# PLT-01-RevB.net
KiCad netlist of a schematic drawn in EAGLE
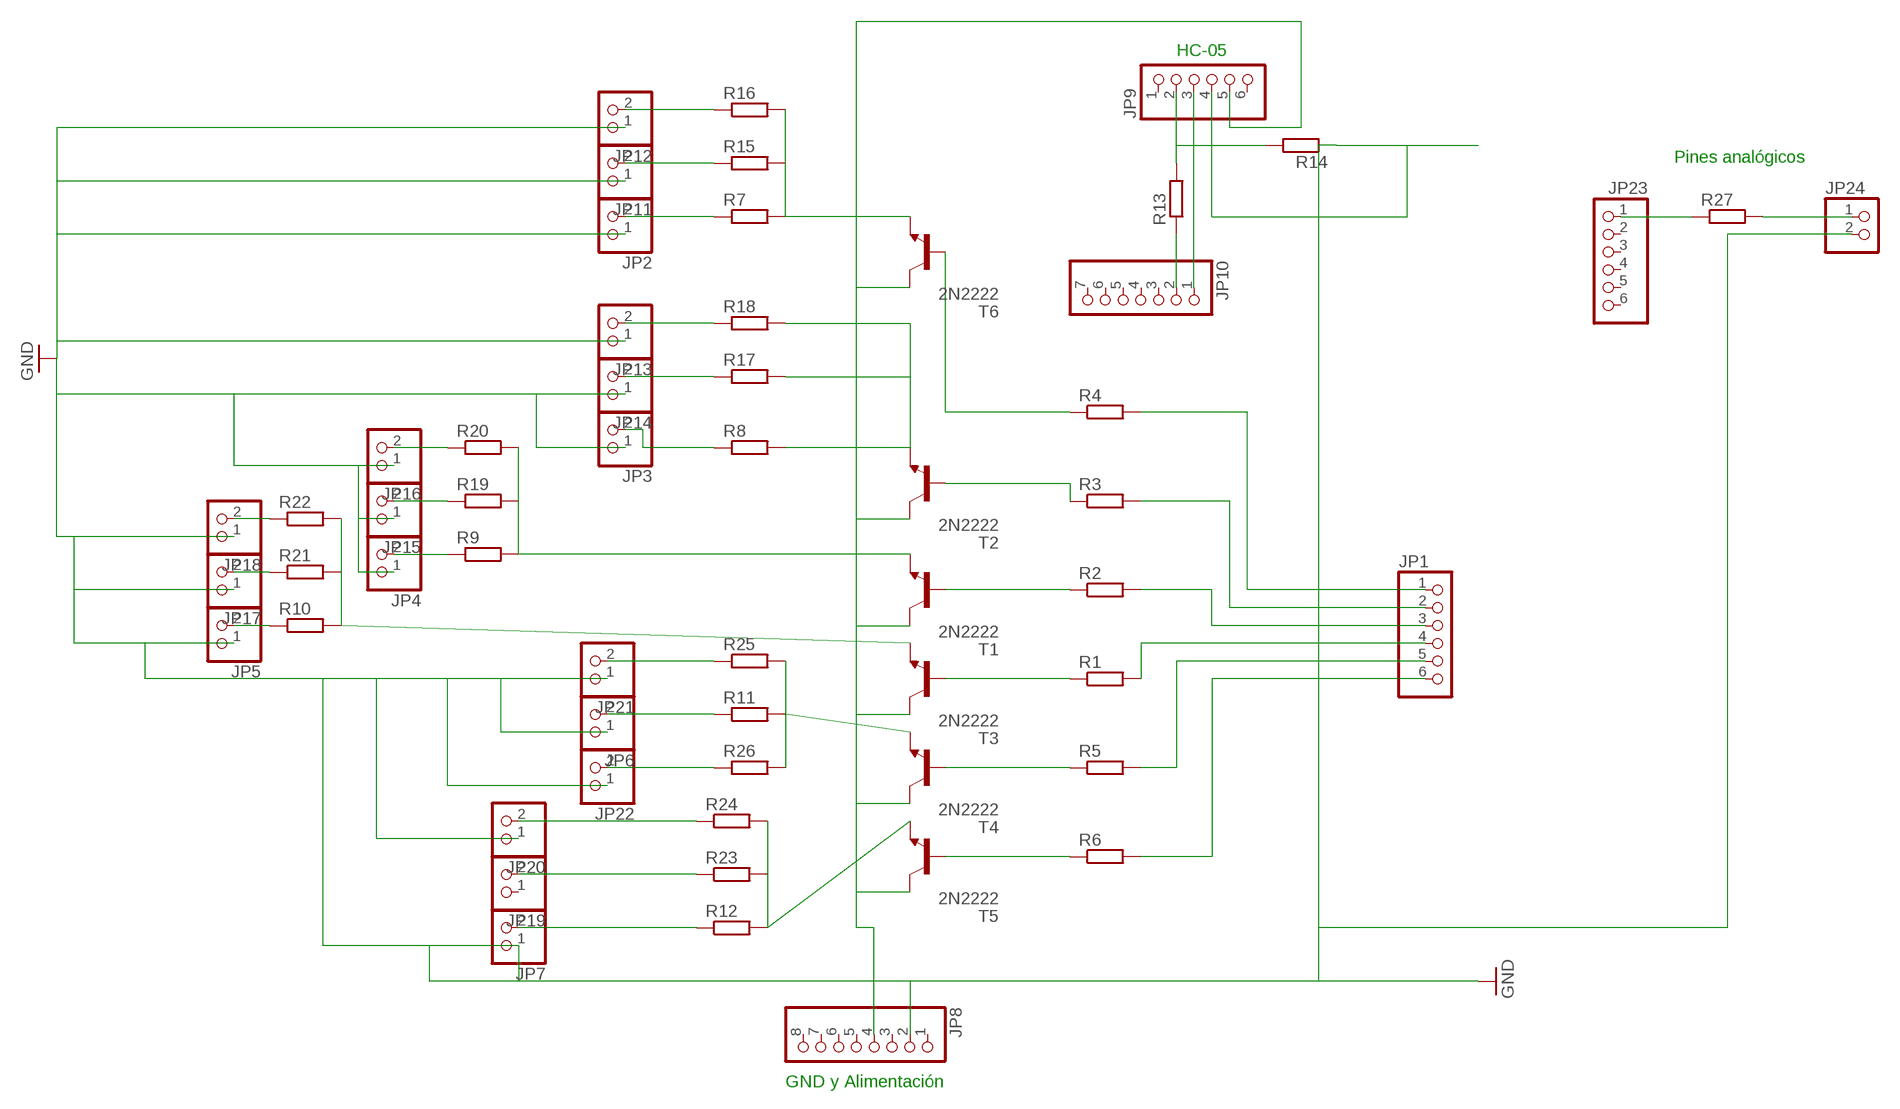
[diagram p0: schematic, sheet 1]

(export (version "E")
  (design (tool "Eeschema 10.0.6"))
  (components
    (comp (ref "JP1")
      (value "PINHD-1X6")
      (footprint "eagle-import:1X06")
      (libsource (lib "eagle-import") (part "PINHD-1X6"))
    )
    (comp (ref "JP2")
      (value "PINHD-1X2")
      (footprint "eagle-import:1X02")
      (libsource (lib "eagle-import") (part "PINHD-1X2"))
    )
    (comp (ref "JP3")
      (value "PINHD-1X2")
      (footprint "eagle-import:1X02")
      (libsource (lib "eagle-import") (part "PINHD-1X2"))
    )
    (comp (ref "JP4")
      (value "PINHD-1X2")
      (footprint "eagle-import:1X02")
      (libsource (lib "eagle-import") (part "PINHD-1X2"))
    )
    (comp (ref "JP5")
      (value "PINHD-1X2")
      (footprint "eagle-import:1X02")
      (libsource (lib "eagle-import") (part "PINHD-1X2"))
    )
    (comp (ref "JP6")
      (value "PINHD-1X2")
      (footprint "eagle-import:1X02")
      (libsource (lib "eagle-import") (part "PINHD-1X2"))
    )
    (comp (ref "JP7")
      (value "PINHD-1X2")
      (footprint "eagle-import:1X02")
      (libsource (lib "eagle-import") (part "PINHD-1X2"))
    )
    (comp (ref "JP8")
      (value "PINHD-1X8")
      (footprint "eagle-import:1X08")
      (libsource (lib "eagle-import") (part "PINHD-1X8"))
    )
    (comp (ref "JP9")
      (value "PINHD-1X6")
      (footprint "eagle-import:1X06")
      (libsource (lib "eagle-import") (part "PINHD-1X6"))
    )
    (comp (ref "JP10")
      (value "PINHD-1X7")
      (footprint "eagle-import:1X07")
      (libsource (lib "eagle-import") (part "PINHD-1X7"))
    )
    (comp (ref "JP11")
      (value "PINHD-1X2")
      (footprint "eagle-import:1X02")
      (libsource (lib "eagle-import") (part "PINHD-1X2"))
    )
    (comp (ref "JP12")
      (value "PINHD-1X2")
      (footprint "eagle-import:1X02")
      (libsource (lib "eagle-import") (part "PINHD-1X2"))
    )
    (comp (ref "JP13")
      (value "PINHD-1X2")
      (footprint "eagle-import:1X02")
      (libsource (lib "eagle-import") (part "PINHD-1X2"))
    )
    (comp (ref "JP14")
      (value "PINHD-1X2")
      (footprint "eagle-import:1X02")
      (libsource (lib "eagle-import") (part "PINHD-1X2"))
    )
    (comp (ref "JP15")
      (value "PINHD-1X2")
      (footprint "eagle-import:1X02")
      (libsource (lib "eagle-import") (part "PINHD-1X2"))
    )
    (comp (ref "JP16")
      (value "PINHD-1X2")
      (footprint "eagle-import:1X02")
      (libsource (lib "eagle-import") (part "PINHD-1X2"))
    )
    (comp (ref "JP17")
      (value "PINHD-1X2")
      (footprint "eagle-import:1X02")
      (libsource (lib "eagle-import") (part "PINHD-1X2"))
    )
    (comp (ref "JP18")
      (value "PINHD-1X2")
      (footprint "eagle-import:1X02")
      (libsource (lib "eagle-import") (part "PINHD-1X2"))
    )
    (comp (ref "JP19")
      (value "PINHD-1X2")
      (footprint "eagle-import:1X02")
      (libsource (lib "eagle-import") (part "PINHD-1X2"))
    )
    (comp (ref "JP20")
      (value "PINHD-1X2")
      (footprint "eagle-import:1X02")
      (libsource (lib "eagle-import") (part "PINHD-1X2"))
    )
    (comp (ref "JP21")
      (value "PINHD-1X2")
      (footprint "eagle-import:1X02")
      (libsource (lib "eagle-import") (part "PINHD-1X2"))
    )
    (comp (ref "JP22")
      (value "PINHD-1X2")
      (footprint "eagle-import:1X02")
      (libsource (lib "eagle-import") (part "PINHD-1X2"))
    )
    (comp (ref "JP23")
      (value "PINHD-1X6")
      (footprint "eagle-import:1X06")
      (libsource (lib "eagle-import") (part "PINHD-1X6"))
    )
    (comp (ref "JP24")
      (value "PINHD-1X2")
      (footprint "eagle-import:1X02")
      (libsource (lib "eagle-import") (part "PINHD-1X2"))
    )
    (comp (ref "R1")
      (value "R-EU_0207/10")
      (footprint "eagle-import:0207_10")
      (libsource (lib "eagle-import") (part "R-EU_0207/10"))
    )
    (comp (ref "R2")
      (value "R-EU_0207/10")
      (footprint "eagle-import:0207_10")
      (libsource (lib "eagle-import") (part "R-EU_0207/10"))
    )
    (comp (ref "R3")
      (value "R-EU_0207/10")
      (footprint "eagle-import:0207_10")
      (libsource (lib "eagle-import") (part "R-EU_0207/10"))
    )
    (comp (ref "R4")
      (value "R-EU_0207/10")
      (footprint "eagle-import:0207_10")
      (libsource (lib "eagle-import") (part "R-EU_0207/10"))
    )
    (comp (ref "R5")
      (value "R-EU_0207/10")
      (footprint "eagle-import:0207_10")
      (libsource (lib "eagle-import") (part "R-EU_0207/10"))
    )
    (comp (ref "R6")
      (value "R-EU_0207/10")
      (footprint "eagle-import:0207_10")
      (libsource (lib "eagle-import") (part "R-EU_0207/10"))
    )
    (comp (ref "R7")
      (value "R-EU_0207/10")
      (footprint "eagle-import:0207_10")
      (libsource (lib "eagle-import") (part "R-EU_0207/10"))
    )
    (comp (ref "R8")
      (value "R-EU_0207/10")
      (footprint "eagle-import:0207_10")
      (libsource (lib "eagle-import") (part "R-EU_0207/10"))
    )
    (comp (ref "R9")
      (value "R-EU_0207/10")
      (footprint "eagle-import:0207_10")
      (libsource (lib "eagle-import") (part "R-EU_0207/10"))
    )
    (comp (ref "R10")
      (value "R-EU_0207/10")
      (footprint "eagle-import:0207_10")
      (libsource (lib "eagle-import") (part "R-EU_0207/10"))
    )
    (comp (ref "R11")
      (value "R-EU_0207/10")
      (footprint "eagle-import:0207_10")
      (libsource (lib "eagle-import") (part "R-EU_0207/10"))
    )
    (comp (ref "R12")
      (value "R-EU_0207/10")
      (footprint "eagle-import:0207_10")
      (libsource (lib "eagle-import") (part "R-EU_0207/10"))
    )
    (comp (ref "R13")
      (value "R-EU_0207/10")
      (footprint "eagle-import:0207_10")
      (libsource (lib "eagle-import") (part "R-EU_0207/10"))
    )
    (comp (ref "R14")
      (value "R-EU_0207/10")
      (footprint "eagle-import:0207_10")
      (libsource (lib "eagle-import") (part "R-EU_0207/10"))
    )
    (comp (ref "R15")
      (value "R-EU_0207/10")
      (footprint "eagle-import:0207_10")
      (libsource (lib "eagle-import") (part "R-EU_0207/10"))
    )
    (comp (ref "R16")
      (value "R-EU_0207/10")
      (footprint "eagle-import:0207_10")
      (libsource (lib "eagle-import") (part "R-EU_0207/10"))
    )
    (comp (ref "R17")
      (value "R-EU_0207/10")
      (footprint "eagle-import:0207_10")
      (libsource (lib "eagle-import") (part "R-EU_0207/10"))
    )
    (comp (ref "R18")
      (value "R-EU_0207/10")
      (footprint "eagle-import:0207_10")
      (libsource (lib "eagle-import") (part "R-EU_0207/10"))
    )
    (comp (ref "R19")
      (value "R-EU_0207/10")
      (footprint "eagle-import:0207_10")
      (libsource (lib "eagle-import") (part "R-EU_0207/10"))
    )
    (comp (ref "R20")
      (value "R-EU_0207/10")
      (footprint "eagle-import:0207_10")
      (libsource (lib "eagle-import") (part "R-EU_0207/10"))
    )
    (comp (ref "R21")
      (value "R-EU_0207/10")
      (footprint "eagle-import:0207_10")
      (libsource (lib "eagle-import") (part "R-EU_0207/10"))
    )
    (comp (ref "R22")
      (value "R-EU_0207/10")
      (footprint "eagle-import:0207_10")
      (libsource (lib "eagle-import") (part "R-EU_0207/10"))
    )
    (comp (ref "R23")
      (value "R-EU_0207/10")
      (footprint "eagle-import:0207_10")
      (libsource (lib "eagle-import") (part "R-EU_0207/10"))
    )
    (comp (ref "R24")
      (value "R-EU_0207/10")
      (footprint "eagle-import:0207_10")
      (libsource (lib "eagle-import") (part "R-EU_0207/10"))
    )
    (comp (ref "R25")
      (value "R-EU_0207/10")
      (footprint "eagle-import:0207_10")
      (libsource (lib "eagle-import") (part "R-EU_0207/10"))
    )
    (comp (ref "R26")
      (value "R-EU_0207/10")
      (footprint "eagle-import:0207_10")
      (libsource (lib "eagle-import") (part "R-EU_0207/10"))
    )
    (comp (ref "R27")
      (value "R-EU_0207/10")
      (footprint "eagle-import:0207_10")
      (libsource (lib "eagle-import") (part "R-EU_0207/10"))
    )
    (comp (ref "T1")
      (value "2N2222")
      (footprint "eagle-import:TO92-EBC-OVAL")
      (libsource (lib "eagle-import") (part "2N2222"))
    )
    (comp (ref "T2")
      (value "2N2222")
      (footprint "eagle-import:TO92-EBC-OVAL")
      (libsource (lib "eagle-import") (part "2N2222"))
    )
    (comp (ref "T3")
      (value "2N2222")
      (footprint "eagle-import:TO92-EBC-OVAL")
      (libsource (lib "eagle-import") (part "2N2222"))
    )
    (comp (ref "T4")
      (value "2N2222")
      (footprint "eagle-import:TO92-EBC-OVAL")
      (libsource (lib "eagle-import") (part "2N2222"))
    )
    (comp (ref "T5")
      (value "2N2222")
      (footprint "eagle-import:TO92-EBC-OVAL")
      (libsource (lib "eagle-import") (part "2N2222"))
    )
    (comp (ref "T6")
      (value "2N2222")
      (footprint "eagle-import:TO92-EBC-OVAL")
      (libsource (lib "eagle-import") (part "2N2222"))
    )
  )
  (nets
    (net (code "1") (name "GND") (class "Default")
      (node (ref "JP11") (pin "1") (pinfunction "1_1") (pintype "passive"))
      (node (ref "JP12") (pin "1") (pinfunction "1_1") (pintype "passive"))
      (node (ref "JP13") (pin "1") (pinfunction "1_1") (pintype "passive"))
      (node (ref "JP14") (pin "1") (pinfunction "1_1") (pintype "passive"))
      (node (ref "JP15") (pin "1") (pinfunction "1_1") (pintype "passive"))
      (node (ref "JP16") (pin "1") (pinfunction "1_1") (pintype "passive"))
      (node (ref "JP17") (pin "1") (pinfunction "1_1") (pintype "passive"))
      (node (ref "JP18") (pin "1") (pinfunction "1_1") (pintype "passive"))
      (node (ref "JP2") (pin "1") (pinfunction "1_1") (pintype "passive"))
      (node (ref "JP20") (pin "1") (pinfunction "1_1") (pintype "passive"))
      (node (ref "JP21") (pin "1") (pinfunction "1_1") (pintype "passive"))
      (node (ref "JP22") (pin "1") (pinfunction "1_1") (pintype "passive"))
      (node (ref "JP24") (pin "2") (pinfunction "2_2") (pintype "passive"))
      (node (ref "JP3") (pin "1") (pinfunction "1_1") (pintype "passive"))
      (node (ref "JP4") (pin "1") (pinfunction "1_1") (pintype "passive"))
      (node (ref "JP5") (pin "1") (pinfunction "1_1") (pintype "passive"))
      (node (ref "JP6") (pin "1") (pinfunction "1_1") (pintype "passive"))
      (node (ref "JP7") (pin "1") (pinfunction "1_1") (pintype "passive"))
      (node (ref "JP8") (pin "2") (pinfunction "2_2") (pintype "passive"))
      (node (ref "JP9") (pin "4") (pinfunction "4_4") (pintype "passive"))
      (node (ref "R14") (pin "1") (pinfunction "1_1") (pintype "passive"))
    )
    (net (code "2") (name "Net-(JP1-Pad1)") (class "Default")
      (node (ref "JP1") (pin "1") (pinfunction "1_1") (pintype "passive"))
      (node (ref "R4") (pin "2") (pinfunction "2_2") (pintype "passive"))
    )
    (net (code "3") (name "Net-(JP1-Pad2)") (class "Default")
      (node (ref "JP1") (pin "2") (pinfunction "2_2") (pintype "passive"))
      (node (ref "R3") (pin "2") (pinfunction "2_2") (pintype "passive"))
    )
    (net (code "4") (name "Net-(JP1-Pad3)") (class "Default")
      (node (ref "JP1") (pin "3") (pinfunction "3_3") (pintype "passive"))
      (node (ref "R2") (pin "2") (pinfunction "2_2") (pintype "passive"))
    )
    (net (code "5") (name "Net-(JP1-Pad4)") (class "Default")
      (node (ref "JP1") (pin "4") (pinfunction "4_4") (pintype "passive"))
      (node (ref "R1") (pin "2") (pinfunction "2_2") (pintype "passive"))
    )
    (net (code "6") (name "Net-(JP1-Pad5)") (class "Default")
      (node (ref "JP1") (pin "5") (pinfunction "5_5") (pintype "passive"))
      (node (ref "R5") (pin "2") (pinfunction "2_2") (pintype "passive"))
    )
    (net (code "7") (name "Net-(JP1-Pad6)") (class "Default")
      (node (ref "JP1") (pin "6") (pinfunction "6_6") (pintype "passive"))
      (node (ref "R6") (pin "2") (pinfunction "2_2") (pintype "passive"))
    )
    (net (code "8") (name "Net-(JP2-Pad2)") (class "Default")
      (node (ref "JP2") (pin "2") (pinfunction "2_2") (pintype "passive"))
      (node (ref "R7") (pin "1") (pinfunction "1_1") (pintype "passive"))
    )
    (net (code "9") (name "Net-(JP3-Pad2)") (class "Default")
      (node (ref "JP3") (pin "2") (pinfunction "2_2") (pintype "passive"))
      (node (ref "R8") (pin "1") (pinfunction "1_1") (pintype "passive"))
    )
    (net (code "10") (name "Net-(JP4-Pad2)") (class "Default")
      (node (ref "JP4") (pin "2") (pinfunction "2_2") (pintype "passive"))
      (node (ref "R9") (pin "1") (pinfunction "1_1") (pintype "passive"))
    )
    (net (code "11") (name "Net-(JP5-Pad2)") (class "Default")
      (node (ref "JP5") (pin "2") (pinfunction "2_2") (pintype "passive"))
      (node (ref "R10") (pin "1") (pinfunction "1_1") (pintype "passive"))
    )
    (net (code "12") (name "Net-(JP6-Pad2)") (class "Default")
      (node (ref "JP6") (pin "2") (pinfunction "2_2") (pintype "passive"))
      (node (ref "R11") (pin "1") (pinfunction "1_1") (pintype "passive"))
    )
    (net (code "13") (name "Net-(JP7-Pad2)") (class "Default")
      (node (ref "JP7") (pin "2") (pinfunction "2_2") (pintype "passive"))
      (node (ref "R12") (pin "1") (pinfunction "1_1") (pintype "passive"))
    )
    (net (code "14") (name "Net-(JP8-Pad4)") (class "Default")
      (node (ref "JP8") (pin "4") (pinfunction "4_4") (pintype "passive"))
      (node (ref "JP9") (pin "5") (pinfunction "5_5") (pintype "passive"))
      (node (ref "T1") (pin "C") (pinfunction "C_C") (pintype "passive"))
      (node (ref "T2") (pin "C") (pinfunction "C_C") (pintype "passive"))
      (node (ref "T3") (pin "C") (pinfunction "C_C") (pintype "passive"))
      (node (ref "T4") (pin "C") (pinfunction "C_C") (pintype "passive"))
      (node (ref "T5") (pin "C") (pinfunction "C_C") (pintype "passive"))
      (node (ref "T6") (pin "C") (pinfunction "C_C") (pintype "passive"))
    )
    (net (code "15") (name "Net-(JP9-Pad2)") (class "Default")
      (node (ref "JP9") (pin "2") (pinfunction "2_2") (pintype "passive"))
      (node (ref "R13") (pin "2") (pinfunction "2_2") (pintype "passive"))
      (node (ref "R14") (pin "2") (pinfunction "2_2") (pintype "passive"))
    )
    (net (code "16") (name "Net-(JP10-Pad1)") (class "Default")
      (node (ref "JP10") (pin "1") (pinfunction "1_1") (pintype "passive"))
      (node (ref "JP9") (pin "3") (pinfunction "3_3") (pintype "passive"))
    )
    (net (code "17") (name "Net-(JP10-Pad2)") (class "Default")
      (node (ref "JP10") (pin "2") (pinfunction "2_2") (pintype "passive"))
      (node (ref "R13") (pin "1") (pinfunction "1_1") (pintype "passive"))
    )
    (net (code "18") (name "Net-(JP11-Pad2)") (class "Default")
      (node (ref "JP11") (pin "2") (pinfunction "2_2") (pintype "passive"))
      (node (ref "R15") (pin "1") (pinfunction "1_1") (pintype "passive"))
    )
    (net (code "19") (name "Net-(JP12-Pad2)") (class "Default")
      (node (ref "JP12") (pin "2") (pinfunction "2_2") (pintype "passive"))
      (node (ref "R16") (pin "1") (pinfunction "1_1") (pintype "passive"))
    )
    (net (code "20") (name "Net-(JP13-Pad2)") (class "Default")
      (node (ref "JP13") (pin "2") (pinfunction "2_2") (pintype "passive"))
      (node (ref "R18") (pin "1") (pinfunction "1_1") (pintype "passive"))
    )
    (net (code "21") (name "Net-(JP14-Pad2)") (class "Default")
      (node (ref "JP14") (pin "2") (pinfunction "2_2") (pintype "passive"))
      (node (ref "R17") (pin "1") (pinfunction "1_1") (pintype "passive"))
    )
    (net (code "22") (name "Net-(JP15-Pad2)") (class "Default")
      (node (ref "JP15") (pin "2") (pinfunction "2_2") (pintype "passive"))
      (node (ref "R19") (pin "1") (pinfunction "1_1") (pintype "passive"))
    )
    (net (code "23") (name "Net-(JP16-Pad2)") (class "Default")
      (node (ref "JP16") (pin "2") (pinfunction "2_2") (pintype "passive"))
      (node (ref "R20") (pin "1") (pinfunction "1_1") (pintype "passive"))
    )
    (net (code "24") (name "Net-(JP17-Pad2)") (class "Default")
      (node (ref "JP17") (pin "2") (pinfunction "2_2") (pintype "passive"))
      (node (ref "R21") (pin "1") (pinfunction "1_1") (pintype "passive"))
    )
    (net (code "25") (name "Net-(JP18-Pad2)") (class "Default")
      (node (ref "JP18") (pin "2") (pinfunction "2_2") (pintype "passive"))
      (node (ref "R22") (pin "1") (pinfunction "1_1") (pintype "passive"))
    )
    (net (code "26") (name "Net-(JP19-Pad2)") (class "Default")
      (node (ref "JP19") (pin "2") (pinfunction "2_2") (pintype "passive"))
      (node (ref "R23") (pin "1") (pinfunction "1_1") (pintype "passive"))
    )
    (net (code "27") (name "Net-(JP20-Pad2)") (class "Default")
      (node (ref "JP20") (pin "2") (pinfunction "2_2") (pintype "passive"))
      (node (ref "R24") (pin "1") (pinfunction "1_1") (pintype "passive"))
    )
    (net (code "28") (name "Net-(JP21-Pad2)") (class "Default")
      (node (ref "JP21") (pin "2") (pinfunction "2_2") (pintype "passive"))
      (node (ref "R25") (pin "1") (pinfunction "1_1") (pintype "passive"))
    )
    (net (code "29") (name "Net-(JP22-Pad2)") (class "Default")
      (node (ref "JP22") (pin "2") (pinfunction "2_2") (pintype "passive"))
      (node (ref "R26") (pin "1") (pinfunction "1_1") (pintype "passive"))
    )
    (net (code "30") (name "Net-(JP23-Pad1)") (class "Default")
      (node (ref "JP23") (pin "1") (pinfunction "1_1") (pintype "passive"))
      (node (ref "R27") (pin "1") (pinfunction "1_1") (pintype "passive"))
    )
    (net (code "31") (name "Net-(JP24-Pad1)") (class "Default")
      (node (ref "JP24") (pin "1") (pinfunction "1_1") (pintype "passive"))
      (node (ref "R27") (pin "2") (pinfunction "2_2") (pintype "passive"))
    )
    (net (code "32") (name "Net-(R1-Pad1)") (class "Default")
      (node (ref "R1") (pin "1") (pinfunction "1_1") (pintype "passive"))
      (node (ref "T3") (pin "B") (pinfunction "B_B") (pintype "passive"))
    )
    (net (code "33") (name "Net-(R2-Pad1)") (class "Default")
      (node (ref "R2") (pin "1") (pinfunction "1_1") (pintype "passive"))
      (node (ref "T1") (pin "B") (pinfunction "B_B") (pintype "passive"))
    )
    (net (code "34") (name "Net-(R3-Pad1)") (class "Default")
      (node (ref "R3") (pin "1") (pinfunction "1_1") (pintype "passive"))
      (node (ref "T2") (pin "B") (pinfunction "B_B") (pintype "passive"))
    )
    (net (code "35") (name "Net-(R4-Pad1)") (class "Default")
      (node (ref "R4") (pin "1") (pinfunction "1_1") (pintype "passive"))
      (node (ref "T6") (pin "B") (pinfunction "B_B") (pintype "passive"))
    )
    (net (code "36") (name "Net-(R5-Pad1)") (class "Default")
      (node (ref "R5") (pin "1") (pinfunction "1_1") (pintype "passive"))
      (node (ref "T4") (pin "B") (pinfunction "B_B") (pintype "passive"))
    )
    (net (code "37") (name "Net-(R6-Pad1)") (class "Default")
      (node (ref "R6") (pin "1") (pinfunction "1_1") (pintype "passive"))
      (node (ref "T5") (pin "B") (pinfunction "B_B") (pintype "passive"))
    )
    (net (code "38") (name "Net-(R10-Pad2)") (class "Default")
      (node (ref "R10") (pin "2") (pinfunction "2_2") (pintype "passive"))
      (node (ref "R21") (pin "2") (pinfunction "2_2") (pintype "passive"))
      (node (ref "R22") (pin "2") (pinfunction "2_2") (pintype "passive"))
      (node (ref "T3") (pin "E") (pinfunction "E_E") (pintype "passive"))
    )
    (net (code "39") (name "Net-(R11-Pad2)") (class "Default")
      (node (ref "R11") (pin "2") (pinfunction "2_2") (pintype "passive"))
      (node (ref "R25") (pin "2") (pinfunction "2_2") (pintype "passive"))
      (node (ref "R26") (pin "2") (pinfunction "2_2") (pintype "passive"))
      (node (ref "T4") (pin "E") (pinfunction "E_E") (pintype "passive"))
    )
    (net (code "40") (name "Net-(R12-Pad2)") (class "Default")
      (node (ref "R12") (pin "2") (pinfunction "2_2") (pintype "passive"))
      (node (ref "R23") (pin "2") (pinfunction "2_2") (pintype "passive"))
      (node (ref "R24") (pin "2") (pinfunction "2_2") (pintype "passive"))
      (node (ref "T5") (pin "E") (pinfunction "E_E") (pintype "passive"))
    )
    (net (code "41") (name "Net-(R15-Pad2)") (class "Default")
      (node (ref "R15") (pin "2") (pinfunction "2_2") (pintype "passive"))
      (node (ref "R16") (pin "2") (pinfunction "2_2") (pintype "passive"))
      (node (ref "R7") (pin "2") (pinfunction "2_2") (pintype "passive"))
      (node (ref "T6") (pin "E") (pinfunction "E_E") (pintype "passive"))
    )
    (net (code "42") (name "Net-(R17-Pad2)") (class "Default")
      (node (ref "R17") (pin "2") (pinfunction "2_2") (pintype "passive"))
      (node (ref "R18") (pin "2") (pinfunction "2_2") (pintype "passive"))
      (node (ref "R8") (pin "2") (pinfunction "2_2") (pintype "passive"))
      (node (ref "T2") (pin "E") (pinfunction "E_E") (pintype "passive"))
    )
    (net (code "43") (name "Net-(R19-Pad2)") (class "Default")
      (node (ref "R19") (pin "2") (pinfunction "2_2") (pintype "passive"))
      (node (ref "R20") (pin "2") (pinfunction "2_2") (pintype "passive"))
      (node (ref "R9") (pin "2") (pinfunction "2_2") (pintype "passive"))
      (node (ref "T1") (pin "E") (pinfunction "E_E") (pintype "passive"))
    )
    (net (code "44") (name "unconnected-(JP8-Pad1)") (class "Default")
      (node (ref "JP8") (pin "1") (pinfunction "1_1") (pintype "passive"))
    )
    (net (code "45") (name "unconnected-(JP8-Pad3)") (class "Default")
      (node (ref "JP8") (pin "3") (pinfunction "3_3") (pintype "passive"))
    )
    (net (code "46") (name "unconnected-(JP8-Pad5)") (class "Default")
      (node (ref "JP8") (pin "5") (pinfunction "5_5") (pintype "passive"))
    )
    (net (code "47") (name "unconnected-(JP8-Pad6)") (class "Default")
      (node (ref "JP8") (pin "6") (pinfunction "6_6") (pintype "passive"))
    )
    (net (code "48") (name "unconnected-(JP8-Pad7)") (class "Default")
      (node (ref "JP8") (pin "7") (pinfunction "7_7") (pintype "passive"))
    )
    (net (code "49") (name "unconnected-(JP8-Pad8)") (class "Default")
      (node (ref "JP8") (pin "8") (pinfunction "8_8") (pintype "passive"))
    )
    (net (code "50") (name "unconnected-(JP9-Pad1)") (class "Default")
      (node (ref "JP9") (pin "1") (pinfunction "1_1") (pintype "passive"))
    )
    (net (code "51") (name "unconnected-(JP9-Pad6)") (class "Default")
      (node (ref "JP9") (pin "6") (pinfunction "6_6") (pintype "passive"))
    )
    (net (code "52") (name "unconnected-(JP10-Pad3)") (class "Default")
      (node (ref "JP10") (pin "3") (pinfunction "3_3") (pintype "passive"))
    )
    (net (code "53") (name "unconnected-(JP10-Pad4)") (class "Default")
      (node (ref "JP10") (pin "4") (pinfunction "4_4") (pintype "passive"))
    )
    (net (code "54") (name "unconnected-(JP10-Pad5)") (class "Default")
      (node (ref "JP10") (pin "5") (pinfunction "5_5") (pintype "passive"))
    )
    (net (code "55") (name "unconnected-(JP10-Pad6)") (class "Default")
      (node (ref "JP10") (pin "6") (pinfunction "6_6") (pintype "passive"))
    )
    (net (code "56") (name "unconnected-(JP10-Pad7)") (class "Default")
      (node (ref "JP10") (pin "7") (pinfunction "7_7") (pintype "passive"))
    )
    (net (code "57") (name "unconnected-(JP19-Pad1)") (class "Default")
      (node (ref "JP19") (pin "1") (pinfunction "1_1") (pintype "passive"))
    )
    (net (code "58") (name "unconnected-(JP23-Pad2)") (class "Default")
      (node (ref "JP23") (pin "2") (pinfunction "2_2") (pintype "passive"))
    )
    (net (code "59") (name "unconnected-(JP23-Pad3)") (class "Default")
      (node (ref "JP23") (pin "3") (pinfunction "3_3") (pintype "passive"))
    )
    (net (code "60") (name "unconnected-(JP23-Pad4)") (class "Default")
      (node (ref "JP23") (pin "4") (pinfunction "4_4") (pintype "passive"))
    )
    (net (code "61") (name "unconnected-(JP23-Pad5)") (class "Default")
      (node (ref "JP23") (pin "5") (pinfunction "5_5") (pintype "passive"))
    )
    (net (code "62") (name "unconnected-(JP23-Pad6)") (class "Default")
      (node (ref "JP23") (pin "6") (pinfunction "6_6") (pintype "passive"))
    )
  )
)
